# 5v_to_3_3V_LDO.net
KiCad netlist of a schematic drawn in Altium Designer
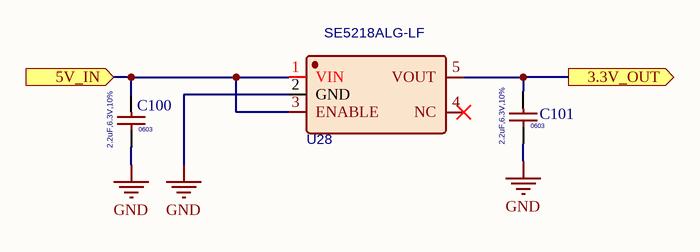
[diagram p0: 5v to 3.3V LDO.SchDoc]

(export (version "E")
  (design (tool "Eeschema 10.0.6"))
  (components
    (comp (ref "C100")
      (value "2.2uF,6.3V,10%")
      (footprint "C0603")
      (description "CAP CER 2.2UF 6.3V X7R 0603")
      (fields
        (field (name "MANUFACTURER") "TDK Corporation")
        (field (name "MPN") "CGA3E1X7R0J225K080AC")
        (field (name "PACKAGE") "0603")
      )
      (libsource (lib "RCL") (part "CGA3E1X7R0J225K080AC"))
    )
    (comp (ref "C101")
      (value "2.2uF,6.3V,10%")
      (footprint "C0603")
      (description "CAP CER 2.2UF 6.3V X7R 0603")
      (fields
        (field (name "MANUFACTURER") "TDK Corporation")
        (field (name "MPN") "CGA3E1X7R0J225K080AC")
        (field (name "PACKAGE") "0603")
      )
      (libsource (lib "RCL") (part "CGA3E1X7R0J225K080AC"))
    )
    (comp (ref "U28")
      (value "SE5218ALG-LF")
      (footprint "SOT-23-5")
      (fields (field (name "MANUFACTURER") "SEAWARD(思旺)"))
      (libsource (lib "IC") (part "SE5218ALG-LF"))
    )
  )
  (nets
    (net (code "1") (name "/3.3V_OUT") (class "Default")
      (node (ref "C101") (pin "1") (pinfunction "1_1") (pintype "passive"))
      (node (ref "U28") (pin "5") (pinfunction "VOUT_5") (pintype "passive"))
    )
    (net (code "2") (name "/5V_IN") (class "Default")
      (node (ref "C100") (pin "1") (pinfunction "1_1") (pintype "passive"))
      (node (ref "U28") (pin "1") (pinfunction "VIN_1") (pintype "passive"))
      (node (ref "U28") (pin "3") (pinfunction "ENABLE_3") (pintype "passive"))
    )
    (net (code "3") (name "GND") (class "Default")
      (node (ref "C100") (pin "2") (pinfunction "2_2") (pintype "passive"))
      (node (ref "C101") (pin "2") (pinfunction "2_2") (pintype "passive"))
      (node (ref "U28") (pin "2") (pinfunction "GND_2") (pintype "passive"))
    )
    (net (code "4") (name "unconnected-(U28-NC-Pad4)") (class "Default")
      (node (ref "U28") (pin "4") (pinfunction "NC_4") (pintype "passive+no_connect"))
    )
  )
)
